# ISOLATOR_LEVEL_SHIFTER.net
KiCad netlist of a schematic drawn in Altium Designer
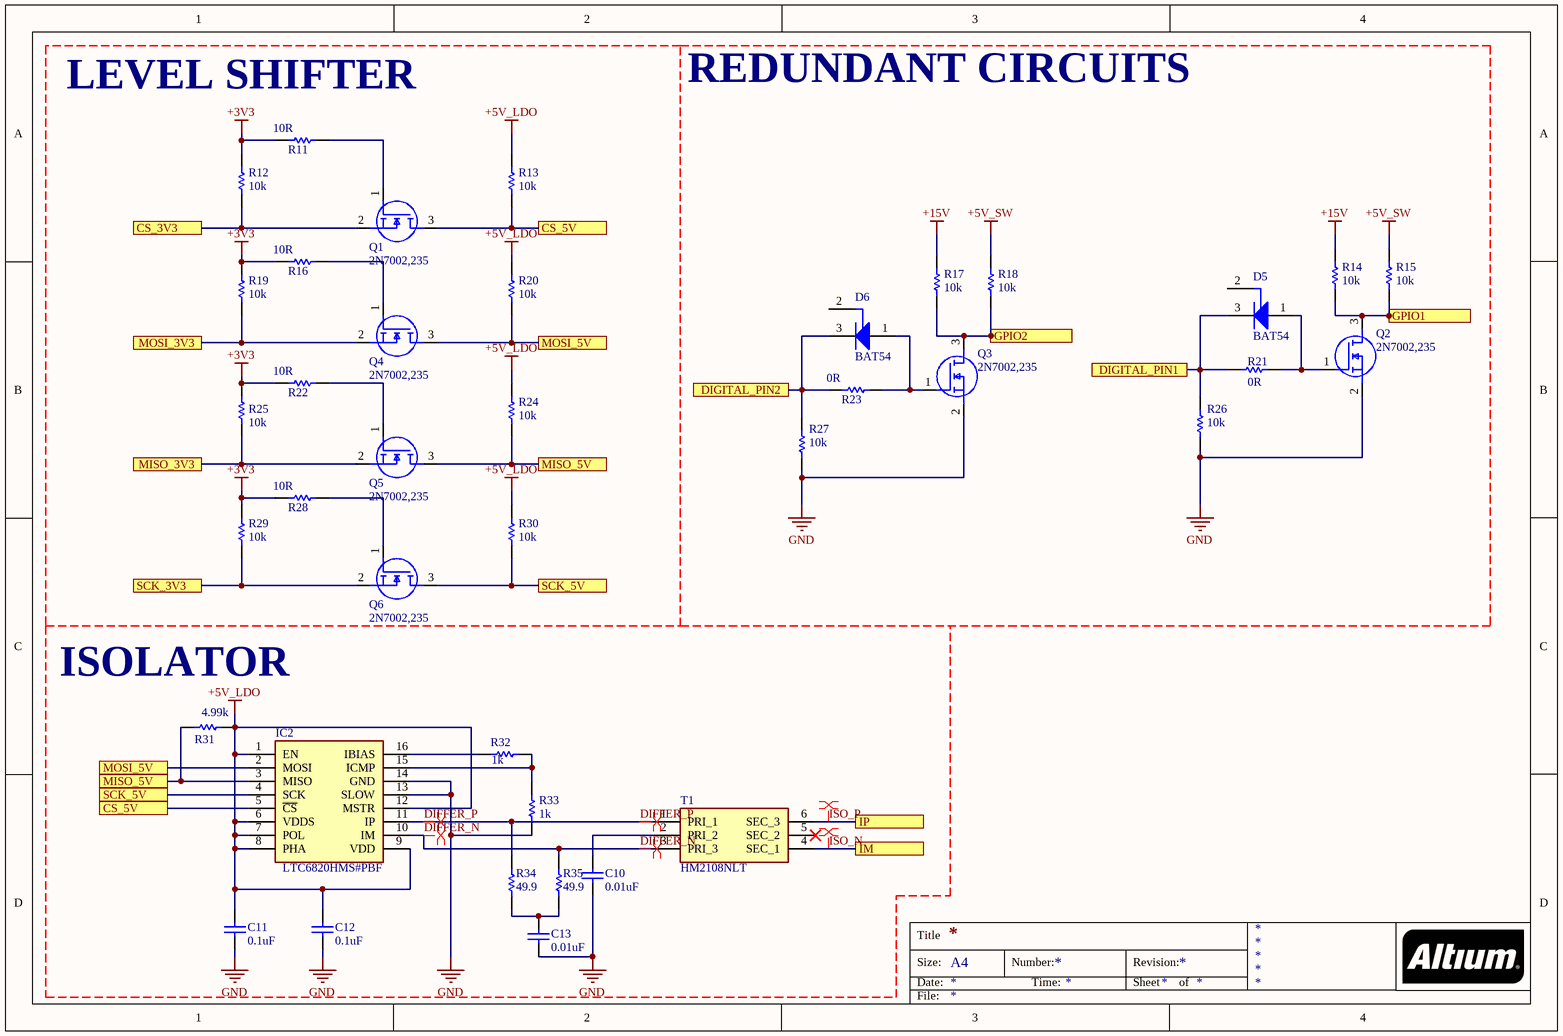
[diagram p0: ISOLATOR_LEVEL SHIFTER.SchDoc]

(export (version "E")
  (design (tool "Eeschema 10.0.6"))
  (components
    (comp (ref "C10")
      (value "0.01uF")
      (footprint "KEMT-1206-2_N")
      (description "CAP, Ceramic, 0.1 uF, +/- 10%, 50 V, -55 to 125 degC, 1206 (3216 Metric), RoHS, Tape and Reel")
      (fields (field (name "MANUFACTURER") "Kemet"))
      (libsource (lib "Schlib1_TSAL_LV_3.1") (part "CMP-1037-04202-2"))
    )
    (comp (ref "C11")
      (value "0.1uF")
      (footprint "KEMT-1206-2_N")
      (description "CAP, Ceramic, 0.1 uF, +/- 10%, 50 V, -55 to 125 degC, 1206 (3216 Metric), RoHS, Tape and Reel")
      (fields (field (name "MANUFACTURER") "Kemet"))
      (libsource (lib "Schlib1_TSAL_LV_3.1") (part "CMP-1037-04202-2"))
    )
    (comp (ref "C12")
      (value "0.1uF")
      (footprint "KEMT-1206-2_N")
      (description "CAP, Ceramic, 0.1 uF, +/- 10%, 50 V, -55 to 125 degC, 1206 (3216 Metric), RoHS, Tape and Reel")
      (fields (field (name "MANUFACTURER") "Kemet"))
      (libsource (lib "Schlib1_TSAL_LV_3.1") (part "CMP-1037-04202-2"))
    )
    (comp (ref "C13")
      (value "0.01uF")
      (footprint "KEMT-1206-2_N")
      (description "CAP, Ceramic, 0.1 uF, +/- 10%, 50 V, -55 to 125 degC, 1206 (3216 Metric), RoHS, Tape and Reel")
      (fields (field (name "MANUFACTURER") "Kemet"))
      (libsource (lib "Schlib1_TSAL_LV_3.1") (part "CMP-1037-04202-2"))
    )
    (comp (ref "D5")
      (value "BAT54")
      (footprint "INF-SOT23_N")
      (description "Silicon Schottky Diode, SOT23, Reel, Green")
      (fields (field (name "MANUFACTURER") "Infineon"))
      (libsource (lib "Schlib1") (part "CMP-1182-00010-1"))
    )
    (comp (ref "D6")
      (value "BAT54")
      (footprint "INF-SOT23_N")
      (description "Silicon Schottky Diode, SOT23, Reel, Green")
      (fields (field (name "MANUFACTURER") "Infineon"))
      (libsource (lib "Schlib1") (part "CMP-1182-00010-1"))
    )
    (comp (ref "IC2")
      (value "LTC6820HMS#PBF")
      (footprint "ltc6820")
      (description "Integrated Circuit")
      (fields (field (name "MOUSER PART NUMBER") "584-LTC6820HMS#PBF"))
      (libsource (lib "Regular_used_components_2D_Symbol") (part "LTC6820HMS#PBF"))
    )
    (comp (ref "Q1")
      (value "2N7002,235")
      (footprint "SamacSys:SOT95P230X110-3N")
      (description "MOSFET (N-Channel)")
      (fields (field (name "MOUSER PART NUMBER") "771-2N7002235"))
      (libsource (lib "*") (part "2N7002,235"))
    )
    (comp (ref "Q2")
      (value "2N7002,235")
      (footprint "SamacSys:SOT95P230X110-3N")
      (description "MOSFET (N-Channel)")
      (fields (field (name "MOUSER PART NUMBER") "771-2N7002235"))
      (libsource (lib "*") (part "2N7002,235"))
    )
    (comp (ref "Q3")
      (value "2N7002,235")
      (footprint "SamacSys:SOT95P230X110-3N")
      (description "MOSFET (N-Channel)")
      (fields (field (name "MOUSER PART NUMBER") "771-2N7002235"))
      (libsource (lib "*") (part "2N7002,235"))
    )
    (comp (ref "Q4")
      (value "2N7002,235")
      (footprint "SamacSys:SOT95P230X110-3N")
      (description "MOSFET (N-Channel)")
      (fields (field (name "MOUSER PART NUMBER") "771-2N7002235"))
      (libsource (lib "*") (part "2N7002,235"))
    )
    (comp (ref "Q5")
      (value "2N7002,235")
      (footprint "SamacSys:SOT95P230X110-3N")
      (description "MOSFET (N-Channel)")
      (fields (field (name "MOUSER PART NUMBER") "771-2N7002235"))
      (libsource (lib "*") (part "2N7002,235"))
    )
    (comp (ref "Q6")
      (value "2N7002,235")
      (footprint "SamacSys:SOT95P230X110-3N")
      (description "MOSFET (N-Channel)")
      (fields (field (name "MOUSER PART NUMBER") "771-2N7002235"))
      (libsource (lib "*") (part "2N7002,235"))
    )
    (comp (ref "R11")
      (value "10R")
      (footprint "RESC3216X60X45NL10T20 - duplicate")
      (fields (field (name "PART NUMBER") "CRCW120647K0FKEA") (field (name "MANUFACTURER") "Vishay Dale"))
      (libsource (lib "Regular_used_components_2D_Symbol") (part "CMP-2003-02213-1"))
    )
    (comp (ref "R12")
      (value "10k")
      (footprint "RESC3216X60X45NL10T20 - duplicate")
      (fields (field (name "PART NUMBER") "CRCW120647K0FKEA") (field (name "MANUFACTURER") "Vishay Dale"))
      (libsource (lib "Regular_used_components_2D_Symbol") (part "CMP-2003-02213-1"))
    )
    (comp (ref "R13")
      (value "10k")
      (footprint "RESC3216X60X45NL10T20 - duplicate")
      (fields (field (name "PART NUMBER") "CRCW120647K0FKEA") (field (name "MANUFACTURER") "Vishay Dale"))
      (libsource (lib "Regular_used_components_2D_Symbol") (part "CMP-2003-02213-1"))
    )
    (comp (ref "R14")
      (value "10k")
      (footprint "RESC3216X60X45NL10T20 - duplicate")
      (fields (field (name "PART NUMBER") "CRCW120647K0FKEA") (field (name "MANUFACTURER") "Vishay Dale"))
      (libsource (lib "Regular_used_components_2D_Symbol") (part "CMP-2003-02213-1"))
    )
    (comp (ref "R15")
      (value "10k")
      (footprint "RESC3216X60X45NL10T20 - duplicate")
      (fields (field (name "PART NUMBER") "CRCW120647K0FKEA") (field (name "MANUFACTURER") "Vishay Dale"))
      (libsource (lib "Regular_used_components_2D_Symbol") (part "CMP-2003-02213-1"))
    )
    (comp (ref "R16")
      (value "10R")
      (footprint "RESC3216X60X45NL10T20 - duplicate")
      (fields (field (name "PART NUMBER") "CRCW120647K0FKEA") (field (name "MANUFACTURER") "Vishay Dale"))
      (libsource (lib "Regular_used_components_2D_Symbol") (part "CMP-2003-02213-1"))
    )
    (comp (ref "R17")
      (value "10k")
      (footprint "RESC3216X60X45NL10T20 - duplicate")
      (fields (field (name "PART NUMBER") "CRCW120647K0FKEA") (field (name "MANUFACTURER") "Vishay Dale"))
      (libsource (lib "Regular_used_components_2D_Symbol") (part "CMP-2003-02213-1"))
    )
    (comp (ref "R18")
      (value "10k")
      (footprint "RESC3216X60X45NL10T20 - duplicate")
      (fields (field (name "PART NUMBER") "CRCW120647K0FKEA") (field (name "MANUFACTURER") "Vishay Dale"))
      (libsource (lib "Regular_used_components_2D_Symbol") (part "CMP-2003-02213-1"))
    )
    (comp (ref "R19")
      (value "10k")
      (footprint "RESC3216X60X45NL10T20 - duplicate")
      (fields (field (name "PART NUMBER") "CRCW120647K0FKEA") (field (name "MANUFACTURER") "Vishay Dale"))
      (libsource (lib "Regular_used_components_2D_Symbol") (part "CMP-2003-02213-1"))
    )
    (comp (ref "R20")
      (value "10k")
      (footprint "RESC3216X60X45NL10T20 - duplicate")
      (fields (field (name "PART NUMBER") "CRCW120647K0FKEA") (field (name "MANUFACTURER") "Vishay Dale"))
      (libsource (lib "Regular_used_components_2D_Symbol") (part "CMP-2003-02213-1"))
    )
    (comp (ref "R21")
      (value "0R")
      (footprint "RESC3216X60X45NL10T20 - duplicate")
      (fields (field (name "PART NUMBER") "CRCW120647K0FKEA") (field (name "MANUFACTURER") "Vishay Dale"))
      (libsource (lib "Regular_used_components_2D_Symbol") (part "CMP-2003-02213-1"))
    )
    (comp (ref "R22")
      (value "10R")
      (footprint "RESC3216X60X45NL10T20 - duplicate")
      (fields (field (name "PART NUMBER") "CRCW120647K0FKEA") (field (name "MANUFACTURER") "Vishay Dale"))
      (libsource (lib "Regular_used_components_2D_Symbol") (part "CMP-2003-02213-1"))
    )
    (comp (ref "R23")
      (value "0R")
      (footprint "RESC3216X60X45NL10T20 - duplicate")
      (fields (field (name "PART NUMBER") "CRCW120647K0FKEA") (field (name "MANUFACTURER") "Vishay Dale"))
      (libsource (lib "Regular_used_components_2D_Symbol") (part "CMP-2003-02213-1"))
    )
    (comp (ref "R24")
      (value "10k")
      (footprint "RESC3216X60X45NL10T20 - duplicate")
      (fields (field (name "PART NUMBER") "CRCW120647K0FKEA") (field (name "MANUFACTURER") "Vishay Dale"))
      (libsource (lib "Regular_used_components_2D_Symbol") (part "CMP-2003-02213-1"))
    )
    (comp (ref "R25")
      (value "10k")
      (footprint "RESC3216X60X45NL10T20 - duplicate")
      (fields (field (name "PART NUMBER") "CRCW120647K0FKEA") (field (name "MANUFACTURER") "Vishay Dale"))
      (libsource (lib "Regular_used_components_2D_Symbol") (part "CMP-2003-02213-1"))
    )
    (comp (ref "R26")
      (value "10k")
      (footprint "RESC3216X60X45NL10T20 - duplicate")
      (fields (field (name "PART NUMBER") "CRCW120647K0FKEA") (field (name "MANUFACTURER") "Vishay Dale"))
      (libsource (lib "Regular_used_components_2D_Symbol") (part "CMP-2003-02213-1"))
    )
    (comp (ref "R27")
      (value "10k")
      (footprint "RESC3216X60X45NL10T20 - duplicate")
      (fields (field (name "PART NUMBER") "CRCW120647K0FKEA") (field (name "MANUFACTURER") "Vishay Dale"))
      (libsource (lib "Regular_used_components_2D_Symbol") (part "CMP-2003-02213-1"))
    )
    (comp (ref "R28")
      (value "10R")
      (footprint "RESC3216X60X45NL10T20 - duplicate")
      (fields (field (name "PART NUMBER") "CRCW120647K0FKEA") (field (name "MANUFACTURER") "Vishay Dale"))
      (libsource (lib "Regular_used_components_2D_Symbol") (part "CMP-2003-02213-1"))
    )
    (comp (ref "R29")
      (value "10k")
      (footprint "RESC3216X60X45NL10T20 - duplicate")
      (fields (field (name "PART NUMBER") "CRCW120647K0FKEA") (field (name "MANUFACTURER") "Vishay Dale"))
      (libsource (lib "Regular_used_components_2D_Symbol") (part "CMP-2003-02213-1"))
    )
    (comp (ref "R30")
      (value "10k")
      (footprint "RESC3216X60X45NL10T20 - duplicate")
      (fields (field (name "PART NUMBER") "CRCW120647K0FKEA") (field (name "MANUFACTURER") "Vishay Dale"))
      (libsource (lib "Regular_used_components_2D_Symbol") (part "CMP-2003-02213-1"))
    )
    (comp (ref "R31")
      (value "4.99k")
      (footprint "RESC3216X60X45NL10T20 - duplicate")
      (fields (field (name "PART NUMBER") "CRCW120647K0FKEA") (field (name "MANUFACTURER") "Vishay Dale"))
      (libsource (lib "Regular_used_components_2D_Symbol") (part "CMP-2003-02213-1"))
    )
    (comp (ref "R32")
      (value "1k")
      (footprint "RESC3216X60X45NL10T20 - duplicate")
      (fields (field (name "PART NUMBER") "CRCW120647K0FKEA") (field (name "MANUFACTURER") "Vishay Dale"))
      (libsource (lib "Regular_used_components_2D_Symbol") (part "CMP-2003-02213-1"))
    )
    (comp (ref "R33")
      (value "1k")
      (footprint "RESC3216X60X45NL10T20 - duplicate")
      (fields (field (name "PART NUMBER") "CRCW120647K0FKEA") (field (name "MANUFACTURER") "Vishay Dale"))
      (libsource (lib "Regular_used_components_2D_Symbol") (part "CMP-2003-02213-1"))
    )
    (comp (ref "R34")
      (value "49.9")
      (footprint "RESC3216X60X45NL10T20 - duplicate")
      (fields (field (name "PART NUMBER") "CRCW120647K0FKEA") (field (name "MANUFACTURER") "Vishay Dale"))
      (libsource (lib "Regular_used_components_2D_Symbol") (part "CMP-2003-02213-1"))
    )
    (comp (ref "R35")
      (value "49.9")
      (footprint "RESC3216X60X45NL10T20 - duplicate")
      (fields (field (name "PART NUMBER") "CRCW120647K0FKEA") (field (name "MANUFACTURER") "Vishay Dale"))
      (libsource (lib "Regular_used_components_2D_Symbol") (part "CMP-2003-02213-1"))
    )
    (comp (ref "T1")
      (value "HM2108NLT")
      (footprint "Regular_used_components_3D_Symbol:HM2108NLT")
      (description "Transformer")
      (fields (field (name "MOUSER PART NUMBER") "673-HM2108NLT"))
      (libsource (lib "*") (part "HM2108NLT"))
    )
  )
  (nets
    (net (code "1") (name "+3V3") (class "Default")
      (node (ref "R11") (pin "2") (pinfunction "2_2") (pintype "passive"))
      (node (ref "R12") (pin "2") (pinfunction "2_2") (pintype "passive"))
      (node (ref "R16") (pin "2") (pinfunction "2_2") (pintype "passive"))
      (node (ref "R19") (pin "2") (pinfunction "2_2") (pintype "passive"))
      (node (ref "R22") (pin "2") (pinfunction "2_2") (pintype "passive"))
      (node (ref "R25") (pin "2") (pinfunction "2_2") (pintype "passive"))
      (node (ref "R28") (pin "2") (pinfunction "2_2") (pintype "passive"))
      (node (ref "R29") (pin "2") (pinfunction "2_2") (pintype "passive"))
    )
    (net (code "2") (name "+5V_LDO") (class "Default")
      (node (ref "C11") (pin "2") (pinfunction "2_2") (pintype "passive"))
      (node (ref "C12") (pin "2") (pinfunction "2_2") (pintype "passive"))
      (node (ref "IC2") (pin "1") (pinfunction "EN_1") (pintype "passive"))
      (node (ref "IC2") (pin "12") (pinfunction "MSTR_12") (pintype "passive"))
      (node (ref "IC2") (pin "6") (pinfunction "VDDS_6") (pintype "passive"))
      (node (ref "IC2") (pin "7") (pinfunction "POL_7") (pintype "passive"))
      (node (ref "IC2") (pin "8") (pinfunction "PHA_8") (pintype "passive"))
      (node (ref "IC2") (pin "9") (pinfunction "VDD_9") (pintype "passive"))
      (node (ref "R13") (pin "2") (pinfunction "2_2") (pintype "passive"))
      (node (ref "R20") (pin "2") (pinfunction "2_2") (pintype "passive"))
      (node (ref "R24") (pin "2") (pinfunction "2_2") (pintype "passive"))
      (node (ref "R30") (pin "2") (pinfunction "2_2") (pintype "passive"))
      (node (ref "R31") (pin "1") (pinfunction "1_1") (pintype "passive"))
    )
    (net (code "3") (name "+5V_SW") (class "Default")
      (node (ref "R15") (pin "1") (pinfunction "1_1") (pintype "passive"))
      (node (ref "R18") (pin "1") (pinfunction "1_1") (pintype "passive"))
    )
    (net (code "4") (name "+15V") (class "Default")
      (node (ref "R14") (pin "1") (pinfunction "1_1") (pintype "passive"))
      (node (ref "R17") (pin "1") (pinfunction "1_1") (pintype "passive"))
    )
    (net (code "5") (name "/CS_3V3") (class "Default")
      (node (ref "Q1") (pin "2") (pinfunction "S_2") (pintype "passive"))
      (node (ref "R12") (pin "1") (pinfunction "1_1") (pintype "passive"))
    )
    (net (code "6") (name "/CS_5V") (class "Default")
      (node (ref "IC2") (pin "5") (pinfunction "~{CS}_5") (pintype "passive"))
      (node (ref "Q1") (pin "3") (pinfunction "D_3") (pintype "passive"))
      (node (ref "R13") (pin "1") (pinfunction "1_1") (pintype "passive"))
    )
    (net (code "7") (name "/DIFFER_N") (class "Default")
      (node (ref "IC2") (pin "10") (pinfunction "IM_10") (pintype "passive"))
      (node (ref "R35") (pin "1") (pinfunction "1_1") (pintype "passive"))
      (node (ref "T1") (pin "3") (pinfunction "PRI_3_3") (pintype "passive"))
    )
    (net (code "8") (name "/DIFFER_P") (class "Default")
      (node (ref "IC2") (pin "11") (pinfunction "IP_11") (pintype "passive"))
      (node (ref "R34") (pin "1") (pinfunction "1_1") (pintype "passive"))
      (node (ref "T1") (pin "1") (pinfunction "PRI_1_1") (pintype "passive"))
    )
    (net (code "9") (name "/DIGITAL_PIN1") (class "Default")
      (node (ref "D5") (pin "3") (pinfunction "K_3") (pintype "passive"))
      (node (ref "R21") (pin "2") (pinfunction "2_2") (pintype "passive"))
      (node (ref "R26") (pin "2") (pinfunction "2_2") (pintype "passive"))
    )
    (net (code "10") (name "/DIGITAL_PIN2") (class "Default")
      (node (ref "D6") (pin "3") (pinfunction "K_3") (pintype "passive"))
      (node (ref "R23") (pin "2") (pinfunction "2_2") (pintype "passive"))
      (node (ref "R27") (pin "2") (pinfunction "2_2") (pintype "passive"))
    )
    (net (code "11") (name "/GPIO1") (class "Default")
      (node (ref "Q2") (pin "3") (pinfunction "D_3") (pintype "passive"))
      (node (ref "R14") (pin "2") (pinfunction "2_2") (pintype "passive"))
      (node (ref "R15") (pin "2") (pinfunction "2_2") (pintype "passive"))
    )
    (net (code "12") (name "/GPIO2") (class "Default")
      (node (ref "Q3") (pin "3") (pinfunction "D_3") (pintype "passive"))
      (node (ref "R17") (pin "2") (pinfunction "2_2") (pintype "passive"))
      (node (ref "R18") (pin "2") (pinfunction "2_2") (pintype "passive"))
    )
    (net (code "13") (name "/ISO_N") (class "Default")
      (node (ref "T1") (pin "4") (pinfunction "SEC_1_4") (pintype "passive"))
    )
    (net (code "14") (name "/ISO_P") (class "Default")
      (node (ref "T1") (pin "6") (pinfunction "SEC_3_6") (pintype "passive"))
    )
    (net (code "15") (name "/MISO_3V3") (class "Default")
      (node (ref "Q5") (pin "2") (pinfunction "S_2") (pintype "passive"))
      (node (ref "R25") (pin "1") (pinfunction "1_1") (pintype "passive"))
    )
    (net (code "16") (name "/MISO_5V") (class "Default")
      (node (ref "IC2") (pin "3") (pinfunction "MISO_3") (pintype "passive"))
      (node (ref "Q5") (pin "3") (pinfunction "D_3") (pintype "passive"))
      (node (ref "R24") (pin "1") (pinfunction "1_1") (pintype "passive"))
      (node (ref "R31") (pin "2") (pinfunction "2_2") (pintype "passive"))
    )
    (net (code "17") (name "/MOSI_3V3") (class "Default")
      (node (ref "Q4") (pin "2") (pinfunction "S_2") (pintype "passive"))
      (node (ref "R19") (pin "1") (pinfunction "1_1") (pintype "passive"))
    )
    (net (code "18") (name "/MOSI_5V") (class "Default")
      (node (ref "IC2") (pin "2") (pinfunction "MOSI_2") (pintype "passive"))
      (node (ref "Q4") (pin "3") (pinfunction "D_3") (pintype "passive"))
      (node (ref "R20") (pin "1") (pinfunction "1_1") (pintype "passive"))
    )
    (net (code "19") (name "/SCK_3V3") (class "Default")
      (node (ref "Q6") (pin "2") (pinfunction "S_2") (pintype "passive"))
      (node (ref "R29") (pin "1") (pinfunction "1_1") (pintype "passive"))
    )
    (net (code "20") (name "/SCK_5V") (class "Default")
      (node (ref "IC2") (pin "4") (pinfunction "SCK_4") (pintype "passive"))
      (node (ref "Q6") (pin "3") (pinfunction "D_3") (pintype "passive"))
      (node (ref "R30") (pin "1") (pinfunction "1_1") (pintype "passive"))
    )
    (net (code "21") (name "GND") (class "Default")
      (node (ref "C10") (pin "1") (pinfunction "1_1") (pintype "passive"))
      (node (ref "C11") (pin "1") (pinfunction "1_1") (pintype "passive"))
      (node (ref "C12") (pin "1") (pinfunction "1_1") (pintype "passive"))
      (node (ref "C13") (pin "1") (pinfunction "1_1") (pintype "passive"))
      (node (ref "IC2") (pin "13") (pinfunction "SLOW_13") (pintype "passive"))
      (node (ref "IC2") (pin "14") (pinfunction "GND_14") (pintype "passive"))
      (node (ref "Q2") (pin "2") (pinfunction "S_2") (pintype "passive"))
      (node (ref "Q3") (pin "2") (pinfunction "S_2") (pintype "passive"))
      (node (ref "R26") (pin "1") (pinfunction "1_1") (pintype "passive"))
      (node (ref "R27") (pin "1") (pinfunction "1_1") (pintype "passive"))
      (node (ref "R33") (pin "1") (pinfunction "1_1") (pintype "passive"))
    )
    (net (code "22") (name "Net-(C13-Pad2)") (class "Default")
      (node (ref "C13") (pin "2") (pinfunction "2_2") (pintype "passive"))
      (node (ref "R34") (pin "2") (pinfunction "2_2") (pintype "passive"))
      (node (ref "R35") (pin "2") (pinfunction "2_2") (pintype "passive"))
    )
    (net (code "23") (name "Net-(D5-A)") (class "Default")
      (node (ref "D5") (pin "1") (pinfunction "A_1") (pintype "passive"))
      (node (ref "Q2") (pin "1") (pinfunction "G_1") (pintype "passive"))
      (node (ref "R21") (pin "1") (pinfunction "1_1") (pintype "passive"))
    )
    (net (code "24") (name "Net-(D6-A)") (class "Default")
      (node (ref "D6") (pin "1") (pinfunction "A_1") (pintype "passive"))
      (node (ref "Q3") (pin "1") (pinfunction "G_1") (pintype "passive"))
      (node (ref "R23") (pin "1") (pinfunction "1_1") (pintype "passive"))
    )
    (net (code "25") (name "Net-(IC2-IBIAS)") (class "Default")
      (node (ref "IC2") (pin "16") (pinfunction "IBIAS_16") (pintype "passive"))
      (node (ref "R32") (pin "2") (pinfunction "2_2") (pintype "passive"))
    )
    (net (code "26") (name "Net-(IC2-ICMP)") (class "Default")
      (node (ref "IC2") (pin "15") (pinfunction "ICMP_15") (pintype "passive"))
      (node (ref "R32") (pin "1") (pinfunction "1_1") (pintype "passive"))
      (node (ref "R33") (pin "2") (pinfunction "2_2") (pintype "passive"))
    )
    (net (code "27") (name "Net-(Q1-G)") (class "Default")
      (node (ref "Q1") (pin "1") (pinfunction "G_1") (pintype "passive"))
      (node (ref "R11") (pin "1") (pinfunction "1_1") (pintype "passive"))
    )
    (net (code "28") (name "Net-(Q4-G)") (class "Default")
      (node (ref "Q4") (pin "1") (pinfunction "G_1") (pintype "passive"))
      (node (ref "R16") (pin "1") (pinfunction "1_1") (pintype "passive"))
    )
    (net (code "29") (name "Net-(Q5-G)") (class "Default")
      (node (ref "Q5") (pin "1") (pinfunction "G_1") (pintype "passive"))
      (node (ref "R22") (pin "1") (pinfunction "1_1") (pintype "passive"))
    )
    (net (code "30") (name "Net-(Q6-G)") (class "Default")
      (node (ref "Q6") (pin "1") (pinfunction "G_1") (pintype "passive"))
      (node (ref "R28") (pin "1") (pinfunction "1_1") (pintype "passive"))
    )
    (net (code "31") (name "Net-(T1-PRI_2)") (class "Default")
      (node (ref "C10") (pin "2") (pinfunction "2_2") (pintype "passive"))
      (node (ref "T1") (pin "2") (pinfunction "PRI_2_2") (pintype "passive"))
    )
    (net (code "32") (name "unconnected-(D5-NC-Pad2)") (class "Default")
      (node (ref "D5") (pin "2") (pinfunction "NC_2") (pintype "passive"))
    )
    (net (code "33") (name "unconnected-(D6-NC-Pad2)") (class "Default")
      (node (ref "D6") (pin "2") (pinfunction "NC_2") (pintype "passive"))
    )
    (net (code "34") (name "unconnected-(T1-SEC_2-Pad5)") (class "Default")
      (node (ref "T1") (pin "5") (pinfunction "SEC_2_5") (pintype "passive+no_connect"))
    )
  )
)
